# DP_UART_RVA.net
KiCad netlist of a schematic drawn in Altium Designer
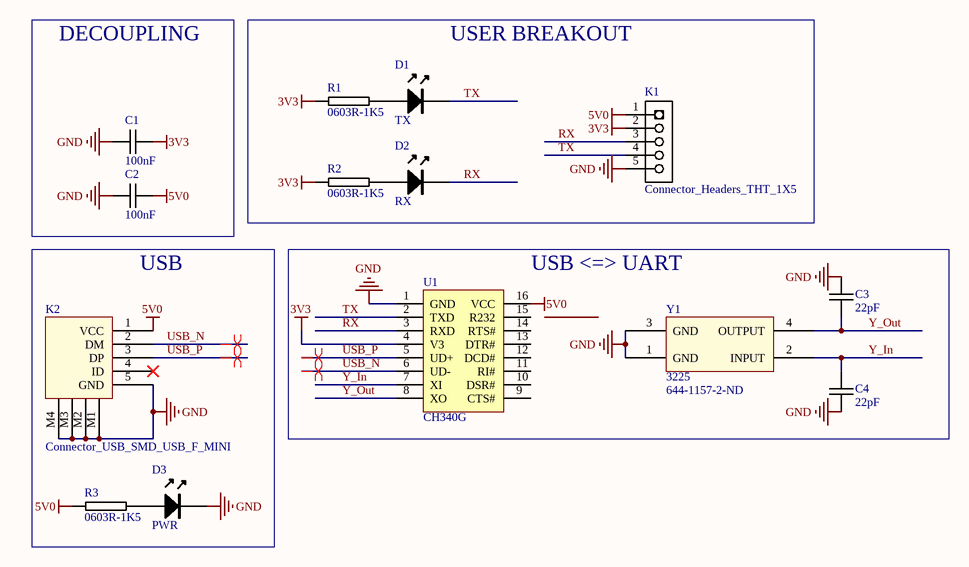
[diagram p0: DP_UART_RVA.SchDoc]

(export (version "E")
  (design (tool "Eeschema 10.0.6"))
  (components
    (comp (ref "C1")
      (value "100nF")
      (footprint "0603C-GENERIC")
      (description "CAPACITOR 0603 CERAMIC GENERIC")
      (libsource (lib "RVA_Altium_Library") (part "Passives_Capacitors_0603_GENERIC"))
    )
    (comp (ref "C2")
      (value "100nF")
      (footprint "0603C-GENERIC")
      (description "CAPACITOR 0603 CERAMIC GENERIC")
      (libsource (lib "RVA_Altium_Library") (part "Passives_Capacitors_0603_GENERIC"))
    )
    (comp (ref "C3")
      (value "22pF")
      (footprint "0603C-GENERIC")
      (description "CAPACITOR 0603 CERAMIC")
      (fields (field (name "TOLERANCE") "±5%") (field (name "MANUFACTURER PART NUMBER") "ECJ-1VC1H220J"))
      (libsource (lib "RVA_Altium_Library") (part "Passives_Capacitors_0603_22PF-50V-C0G-PAN"))
    )
    (comp (ref "C4")
      (value "22pF")
      (footprint "0603C-GENERIC")
      (description "CAPACITOR 0603 CERAMIC")
      (fields (field (name "TOLERANCE") "±5%") (field (name "MANUFACTURER PART NUMBER") "ECJ-1VC1H220J"))
      (libsource (lib "RVA_Altium_Library") (part "Passives_Capacitors_0603_22PF-50V-C0G-PAN"))
    )
    (comp (ref "D1")
      (value "TX")
      (footprint "0805LED")
      (libsource (lib "RVA_Altium_Library") (part "LED_SMD_0805"))
    )
    (comp (ref "D2")
      (value "RX")
      (footprint "0805LED")
      (libsource (lib "RVA_Altium_Library") (part "LED_SMD_0805"))
    )
    (comp (ref "D3")
      (value "PWR")
      (footprint "0805LED")
      (libsource (lib "RVA_Altium_Library") (part "LED_SMD_0805"))
    )
    (comp (ref "K1")
      (value "Connector_Headers_THT_1X5")
      (footprint "HEADER-1X5")
      (description "PINHEADER 1X5")
      (libsource (lib "RVA_Altium_Library") (part "Connector_Headers_THT_1X5"))
    )
    (comp (ref "K2")
      (value "Connector_USB_SMD_USB_F_MINI")
      (footprint "USB_F_MINI")
      (description "MINI USB B FEMALE")
      (libsource (lib "RVA_Altium_Library") (part "Connector_USB_SMD_USB_F_MINI"))
    )
    (comp (ref "R1")
      (value "0603R-1K5")
      (footprint "0603R-1k5")
      (description "GENERIC RESISTOR 0603")
      (fields (field (name "MANUFACTURER PART NUMBER") "RMCF 1/16 15K 1% R") (field (name "TOLERANCE") "±1%"))
      (libsource (lib "RVA_Passives_Resistors_0603") (part "0603R-1K5"))
    )
    (comp (ref "R2")
      (value "0603R-1K5")
      (footprint "0603R-1k5")
      (description "GENERIC RESISTOR 0603")
      (fields (field (name "MANUFACTURER PART NUMBER") "RMCF 1/16 15K 1% R") (field (name "TOLERANCE") "±1%"))
      (libsource (lib "RVA_Passives_Resistors_0603") (part "0603R-1K5"))
    )
    (comp (ref "R3")
      (value "0603R-1K5")
      (footprint "0603R-1k5")
      (description "GENERIC RESISTOR 0603")
      (fields (field (name "MANUFACTURER PART NUMBER") "RMCF 1/16 15K 1% R") (field (name "TOLERANCE") "±1%"))
      (libsource (lib "RVA_Passives_Resistors_0603") (part "0603R-1K5"))
    )
    (comp (ref "U1") (value "CH340G") (footprint "SO16") (libsource (lib "CH340") (part "CH340G")))
    (comp (ref "Y1")
      (value "3225")
      (footprint "XTAL 3225")
      (fields (field (name "SUPPLIER PART NUMBER 1") "644-1157-2-ND"))
      (libsource (lib "RVA_Reference_Crystal Oscillator_SMD") (part "3225 Quartz"))
    )
  )
  (nets
    (net (code "1") (name "/RX") (class "Default")
      (node (ref "D2") (pin "K") (pintype "passive"))
      (node (ref "K1") (pin "3") (pintype "passive"))
      (node (ref "U1") (pin "3") (pinfunction "RXD_3") (pintype "passive"))
    )
    (net (code "2") (name "/TX") (class "Default")
      (node (ref "D1") (pin "K") (pintype "passive"))
      (node (ref "K1") (pin "4") (pintype "passive"))
      (node (ref "U1") (pin "2") (pinfunction "TXD_2") (pintype "passive"))
    )
    (net (code "3") (name "/USB_N") (class "Default")
      (node (ref "K2") (pin "2") (pinfunction "DM_2") (pintype "passive"))
      (node (ref "U1") (pin "6") (pinfunction "UD-_6") (pintype "passive"))
    )
    (net (code "4") (name "/USB_P") (class "Default")
      (node (ref "K2") (pin "3") (pinfunction "DP_3") (pintype "passive"))
      (node (ref "U1") (pin "5") (pinfunction "UD+_5") (pintype "passive"))
    )
    (net (code "5") (name "/Y_In") (class "Default")
      (node (ref "C4") (pin "1") (pintype "passive"))
      (node (ref "U1") (pin "7") (pinfunction "XI_7") (pintype "passive"))
      (node (ref "Y1") (pin "2") (pinfunction "INPUT_2") (pintype "passive"))
    )
    (net (code "6") (name "/Y_Out") (class "Default")
      (node (ref "C3") (pin "2") (pintype "passive"))
      (node (ref "U1") (pin "8") (pinfunction "XO_8") (pintype "passive"))
      (node (ref "Y1") (pin "4") (pinfunction "OUTPUT_4") (pintype "passive"))
    )
    (net (code "7") (name "3V3") (class "Default")
      (node (ref "C1") (pin "2") (pintype "passive"))
      (node (ref "K1") (pin "2") (pintype "passive"))
      (node (ref "R1") (pin "1") (pintype "passive"))
      (node (ref "R2") (pin "1") (pintype "passive"))
      (node (ref "U1") (pin "4") (pinfunction "V3_4") (pintype "passive"))
    )
    (net (code "8") (name "5V0") (class "Default")
      (node (ref "C2") (pin "2") (pintype "passive"))
      (node (ref "K1") (pin "1") (pintype "passive"))
      (node (ref "K2") (pin "1") (pinfunction "VCC_1") (pintype "passive"))
      (node (ref "R3") (pin "1") (pintype "passive"))
      (node (ref "U1") (pin "16") (pinfunction "VCC_16") (pintype "passive"))
    )
    (net (code "9") (name "GND") (class "Default")
      (node (ref "C1") (pin "1") (pintype "passive"))
      (node (ref "C2") (pin "1") (pintype "passive"))
      (node (ref "C3") (pin "1") (pintype "passive"))
      (node (ref "C4") (pin "2") (pintype "passive"))
      (node (ref "D3") (pin "K") (pintype "passive"))
      (node (ref "K1") (pin "5") (pintype "passive"))
      (node (ref "K2") (pin "5") (pinfunction "GND_5") (pintype "passive"))
      (node (ref "K2") (pin "M1") (pinfunction "M1_M1") (pintype "power_in"))
      (node (ref "K2") (pin "M2") (pinfunction "M2_M2") (pintype "power_in"))
      (node (ref "K2") (pin "M3") (pinfunction "M3_M3") (pintype "power_in"))
      (node (ref "K2") (pin "M4") (pinfunction "M4_M4") (pintype "power_in"))
      (node (ref "U1") (pin "1") (pinfunction "GND_1") (pintype "passive"))
      (node (ref "Y1") (pin "1") (pinfunction "GND_1") (pintype "passive"))
      (node (ref "Y1") (pin "3") (pinfunction "GND_3") (pintype "passive"))
    )
    (net (code "10") (name "Net-(D1-PadA)") (class "Default")
      (node (ref "D1") (pin "A") (pintype "passive"))
      (node (ref "R1") (pin "2") (pintype "passive"))
    )
    (net (code "11") (name "Net-(D2-PadA)") (class "Default")
      (node (ref "D2") (pin "A") (pintype "passive"))
      (node (ref "R2") (pin "2") (pintype "passive"))
    )
    (net (code "12") (name "Net-(D3-PadA)") (class "Default")
      (node (ref "D3") (pin "A") (pintype "passive"))
      (node (ref "R3") (pin "2") (pintype "passive"))
    )
    (net (code "13") (name "unconnected-(K2-ID-Pad4)") (class "Default")
      (node (ref "K2") (pin "4") (pinfunction "ID_4") (pintype "passive+no_connect"))
    )
    (net (code "14") (name "unconnected-(U1-CTS#-Pad9)") (class "Default")
      (node (ref "U1") (pin "9") (pinfunction "CTS#_9") (pintype "passive"))
    )
    (net (code "15") (name "unconnected-(U1-DCD#-Pad12)") (class "Default")
      (node (ref "U1") (pin "12") (pinfunction "DCD#_12") (pintype "passive"))
    )
    (net (code "16") (name "unconnected-(U1-DSR#-Pad10)") (class "Default")
      (node (ref "U1") (pin "10") (pinfunction "DSR#_10") (pintype "passive"))
    )
    (net (code "17") (name "unconnected-(U1-DTR#-Pad13)") (class "Default")
      (node (ref "U1") (pin "13") (pinfunction "DTR#_13") (pintype "passive"))
    )
    (net (code "18") (name "unconnected-(U1-R232-Pad15)") (class "Default")
      (node (ref "U1") (pin "15") (pinfunction "R232_15") (pintype "passive"))
    )
    (net (code "19") (name "unconnected-(U1-RI#-Pad11)") (class "Default")
      (node (ref "U1") (pin "11") (pinfunction "RI#_11") (pintype "passive"))
    )
    (net (code "20") (name "unconnected-(U1-RTS#-Pad14)") (class "Default")
      (node (ref "U1") (pin "14") (pinfunction "RTS#_14") (pintype "passive"))
    )
  )
)
